# sensor_v3b_trim.net
KiCad netlist of a schematic drawn in EAGLE
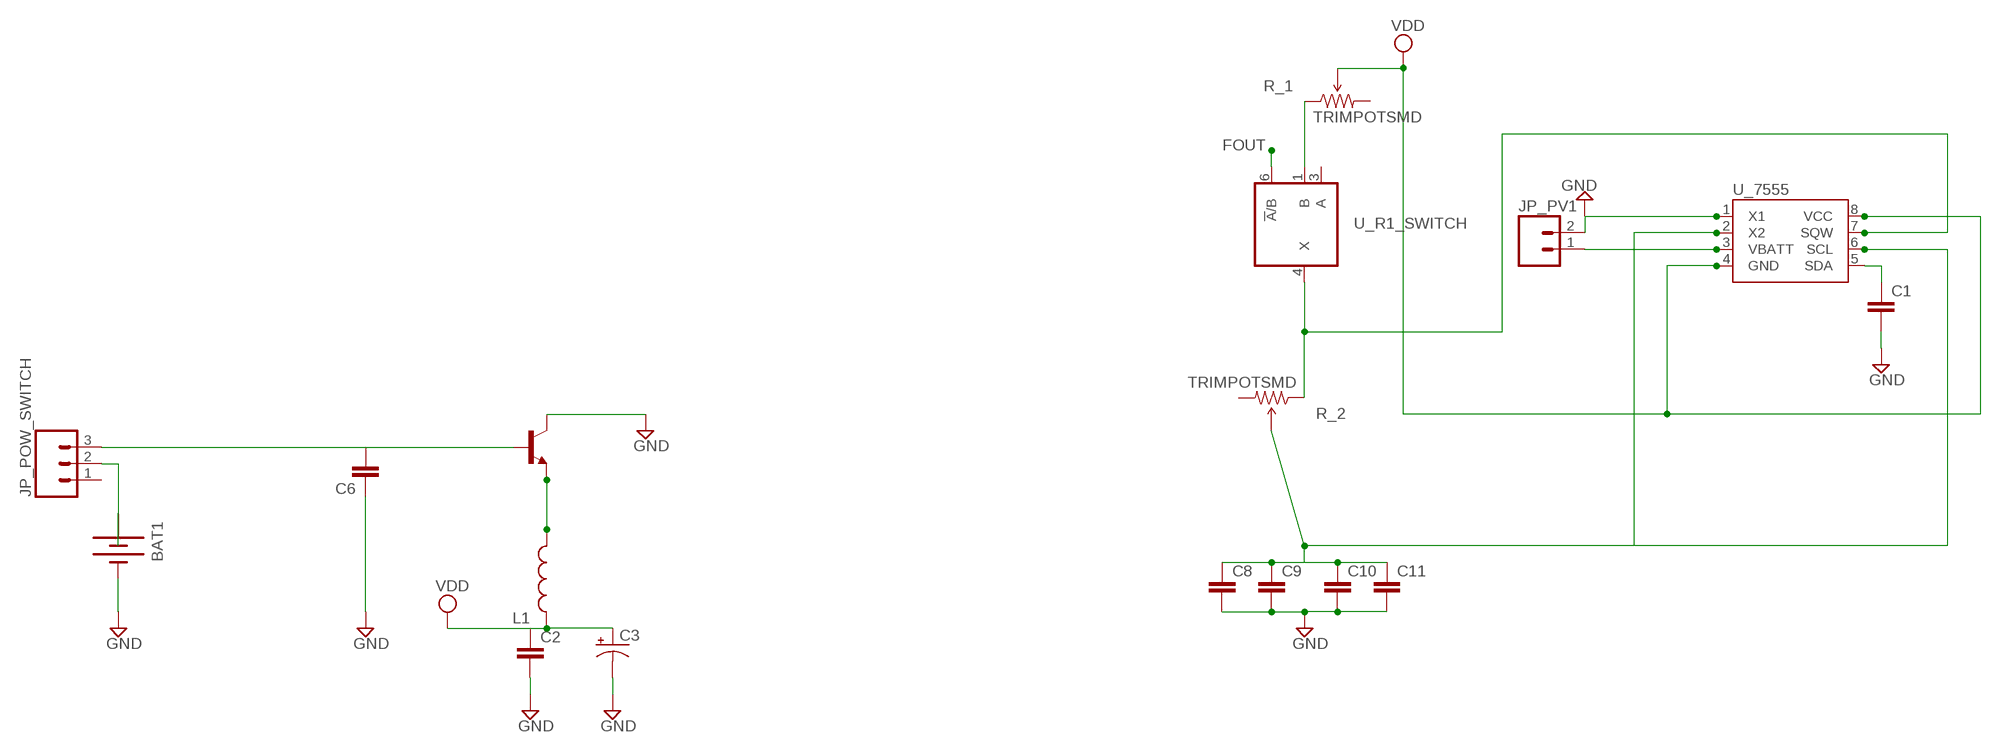
[diagram p0: schematic, sheet 1]

(export (version "E")
  (design (tool "Eeschema 10.0.6"))
  (components
    (comp (ref "BAT1")
      (value "BATTERY20PTH_LAB")
      (footprint "eagle-import:BATTCOM_20MM_PTH")
      (libsource (lib "eagle-import") (part "BATTERY20PTH_LAB"))
    )
    (comp (ref "C1")
      (value "CAP0603-CAP")
      (footprint "eagle-import:0603-CAP")
      (libsource (lib "eagle-import") (part "SparkFun-Capacitors_CAP0603-CAP"))
    )
    (comp (ref "C2")
      (value "CAP0603-CAP")
      (footprint "eagle-import:0603-CAP")
      (libsource (lib "eagle-import") (part "SparkFun-Capacitors_CAP0603-CAP"))
    )
    (comp (ref "C3")
      (value "CAP_POL1206")
      (footprint "eagle-import:EIA3216")
      (libsource (lib "eagle-import") (part "CAP_POL1206"))
    )
    (comp (ref "C6")
      (value "CAP0603-CAP")
      (footprint "eagle-import:0603-CAP")
      (libsource (lib "eagle-import") (part "SparkFun-Capacitors_CAP0603-CAP"))
    )
    (comp (ref "C8")
      (value "CAP0805")
      (footprint "eagle-import:0805")
      (libsource (lib "eagle-import") (part "CAP0805"))
    )
    (comp (ref "C9")
      (value "CAP0805")
      (footprint "eagle-import:0805")
      (libsource (lib "eagle-import") (part "CAP0805"))
    )
    (comp (ref "C10")
      (value "CAP0805")
      (footprint "eagle-import:0805")
      (libsource (lib "eagle-import") (part "CAP0805"))
    )
    (comp (ref "C11")
      (value "CAP0805")
      (footprint "eagle-import:0805")
      (libsource (lib "eagle-import") (part "CAP0805"))
    )
    (comp (ref "JP_POW_SWITCH")
      (value "M03LOCK")
      (footprint "eagle-import:1X03_LOCK")
      (libsource (lib "eagle-import") (part "M03LOCK"))
    )
    (comp (ref "JP_PV1")
      (value "M02LOCK")
      (footprint "eagle-import:1X02_LOCK")
      (libsource (lib "eagle-import") (part "M02LOCK"))
    )
    (comp (ref "L1")
      (value "INDUCTOR0603")
      (footprint "eagle-import:0603")
      (libsource (lib "eagle-import") (part "INDUCTOR0603"))
    )
    (comp (ref "R_1")
      (value "TRIMPOTSMD")
      (footprint "eagle-import:TRIMPOT-3MM")
      (libsource (lib "eagle-import") (part "TRIMPOTSMD"))
    )
    (comp (ref "R_2")
      (value "TRIMPOTSMD")
      (footprint "eagle-import:TRIMPOT-3MM")
      (libsource (lib "eagle-import") (part "TRIMPOTSMD"))
    )
    (comp (ref "U_7555")
      (value "DS1307SO8")
      (footprint "eagle-import:SO08")
      (libsource (lib "eagle-import") (part "DS1307SO8"))
    )
    (comp (ref "U_R1_SWITCH")
      (value "741G3157DCKR")
      (footprint "eagle-import:DCK_R-PDSO-G6")
      (libsource (lib "eagle-import") (part "741G3157DCKR"))
    )
    (comp (ref "U_VREF")
      (value "TRANSISTOR_NPNSOT23-3")
      (footprint "eagle-import:SOT23-3")
      (libsource (lib "eagle-import") (part "TRANSISTOR_NPNSOT23-3"))
    )
  )
  (nets
    (net (code "1") (name "/FOUT") (class "Default")
      (node (ref "JP_PV1") (pin "1") (pinfunction "1_1") (pintype "passive"))
      (node (ref "U_7555") (pin "3") (pinfunction "VBATT_3") (pintype "bidirectional"))
      (node (ref "U_R1_SWITCH") (pin "6") (pinfunction "~{A}/B_6") (pintype "input"))
    )
    (net (code "2") (name "/P2") (class "Default")
      (node (ref "C10") (pin "1") (pinfunction "1_1") (pintype "passive"))
      (node (ref "C11") (pin "1") (pinfunction "1_1") (pintype "passive"))
      (node (ref "C8") (pin "1") (pinfunction "1_1") (pintype "passive"))
      (node (ref "C9") (pin "1") (pinfunction "1_1") (pintype "passive"))
      (node (ref "R_2") (pin "2") (pinfunction "WIPER_2") (pintype "passive"))
      (node (ref "U_7555") (pin "2") (pinfunction "X2_2") (pintype "bidirectional"))
      (node (ref "U_7555") (pin "6") (pinfunction "SCL_6") (pintype "bidirectional"))
    )
    (net (code "3") (name "GND") (class "Default")
      (node (ref "BAT1") (pin "2") (pinfunction "-_2") (pintype "power_in"))
      (node (ref "C1") (pin "2") (pinfunction "2_2") (pintype "passive"))
      (node (ref "C10") (pin "2") (pinfunction "2_2") (pintype "passive"))
      (node (ref "C11") (pin "2") (pinfunction "2_2") (pintype "passive"))
      (node (ref "C2") (pin "2") (pinfunction "2_2") (pintype "passive"))
      (node (ref "C3") (pin "C") (pinfunction "-_C") (pintype "passive"))
      (node (ref "C6") (pin "1") (pinfunction "1_1") (pintype "passive"))
      (node (ref "C8") (pin "2") (pinfunction "2_2") (pintype "passive"))
      (node (ref "C9") (pin "2") (pinfunction "2_2") (pintype "passive"))
      (node (ref "JP_PV1") (pin "2") (pinfunction "2_2") (pintype "passive"))
      (node (ref "U_7555") (pin "1") (pinfunction "X1_1") (pintype "bidirectional"))
      (node (ref "U_VREF") (pin "3") (pinfunction "C_3") (pintype "passive"))
    )
    (net (code "4") (name "Net-(BAT1-+)") (class "Default")
      (node (ref "BAT1") (pin "1") (pinfunction "+_1") (pintype "power_in"))
      (node (ref "JP_POW_SWITCH") (pin "2") (pinfunction "2_2") (pintype "passive"))
    )
    (net (code "5") (name "Net-(R_1-CCW)") (class "Default")
      (node (ref "R_1") (pin "1") (pinfunction "CCW_1") (pintype "passive"))
      (node (ref "U_R1_SWITCH") (pin "1") (pinfunction "B_1") (pintype "bidirectional"))
    )
    (net (code "6") (name "Net-(R_2-CCW)") (class "Default")
      (node (ref "R_2") (pin "1") (pinfunction "CCW_1") (pintype "passive"))
      (node (ref "U_7555") (pin "7") (pinfunction "SQW_7") (pintype "bidirectional"))
      (node (ref "U_R1_SWITCH") (pin "4") (pinfunction "X_4") (pintype "bidirectional"))
    )
    (net (code "7") (name "Net-(U_7555-SDA)") (class "Default")
      (node (ref "C1") (pin "1") (pinfunction "1_1") (pintype "passive"))
      (node (ref "U_7555") (pin "5") (pinfunction "SDA_5") (pintype "bidirectional"))
    )
    (net (code "8") (name "Net-(U_VREF-B)") (class "Default")
      (node (ref "C6") (pin "2") (pinfunction "2_2") (pintype "passive"))
      (node (ref "JP_POW_SWITCH") (pin "3") (pinfunction "3_3") (pintype "passive"))
      (node (ref "U_VREF") (pin "1") (pinfunction "B_1") (pintype "passive"))
    )
    (net (code "9") (name "Net-(U_VREF-E)") (class "Default")
      (node (ref "L1") (pin "2") (pinfunction "2_2") (pintype "passive"))
      (node (ref "U_VREF") (pin "2") (pinfunction "E_2") (pintype "passive"))
    )
    (net (code "10") (name "VDD") (class "Default")
      (node (ref "C2") (pin "1") (pinfunction "1_1") (pintype "passive"))
      (node (ref "C3") (pin "A") (pinfunction "+_A") (pintype "passive"))
      (node (ref "L1") (pin "1") (pinfunction "1_1") (pintype "passive"))
      (node (ref "R_1") (pin "2") (pinfunction "WIPER_2") (pintype "passive"))
      (node (ref "U_7555") (pin "4") (pinfunction "GND_4") (pintype "bidirectional"))
      (node (ref "U_7555") (pin "8") (pinfunction "VCC_8") (pintype "bidirectional"))
    )
    (net (code "11") (name "unconnected-(JP_POW_SWITCH-Pad1)") (class "Default")
      (node (ref "JP_POW_SWITCH") (pin "1") (pinfunction "1_1") (pintype "passive"))
    )
    (net (code "12") (name "unconnected-(R_1-CW-Pad3)") (class "Default")
      (node (ref "R_1") (pin "3") (pinfunction "CW_3") (pintype "passive"))
    )
    (net (code "13") (name "unconnected-(R_2-CW-Pad3)") (class "Default")
      (node (ref "R_2") (pin "3") (pinfunction "CW_3") (pintype "passive"))
    )
    (net (code "14") (name "unconnected-(U_R1_SWITCHA-A-Pad3)") (class "Default")
      (node (ref "U_R1_SWITCH") (pin "3") (pinfunction "A_3") (pintype "bidirectional"))
    )
  )
)
